# X13_Power_Distribution_B.net
KiCad netlist of a schematic drawn in EAGLE
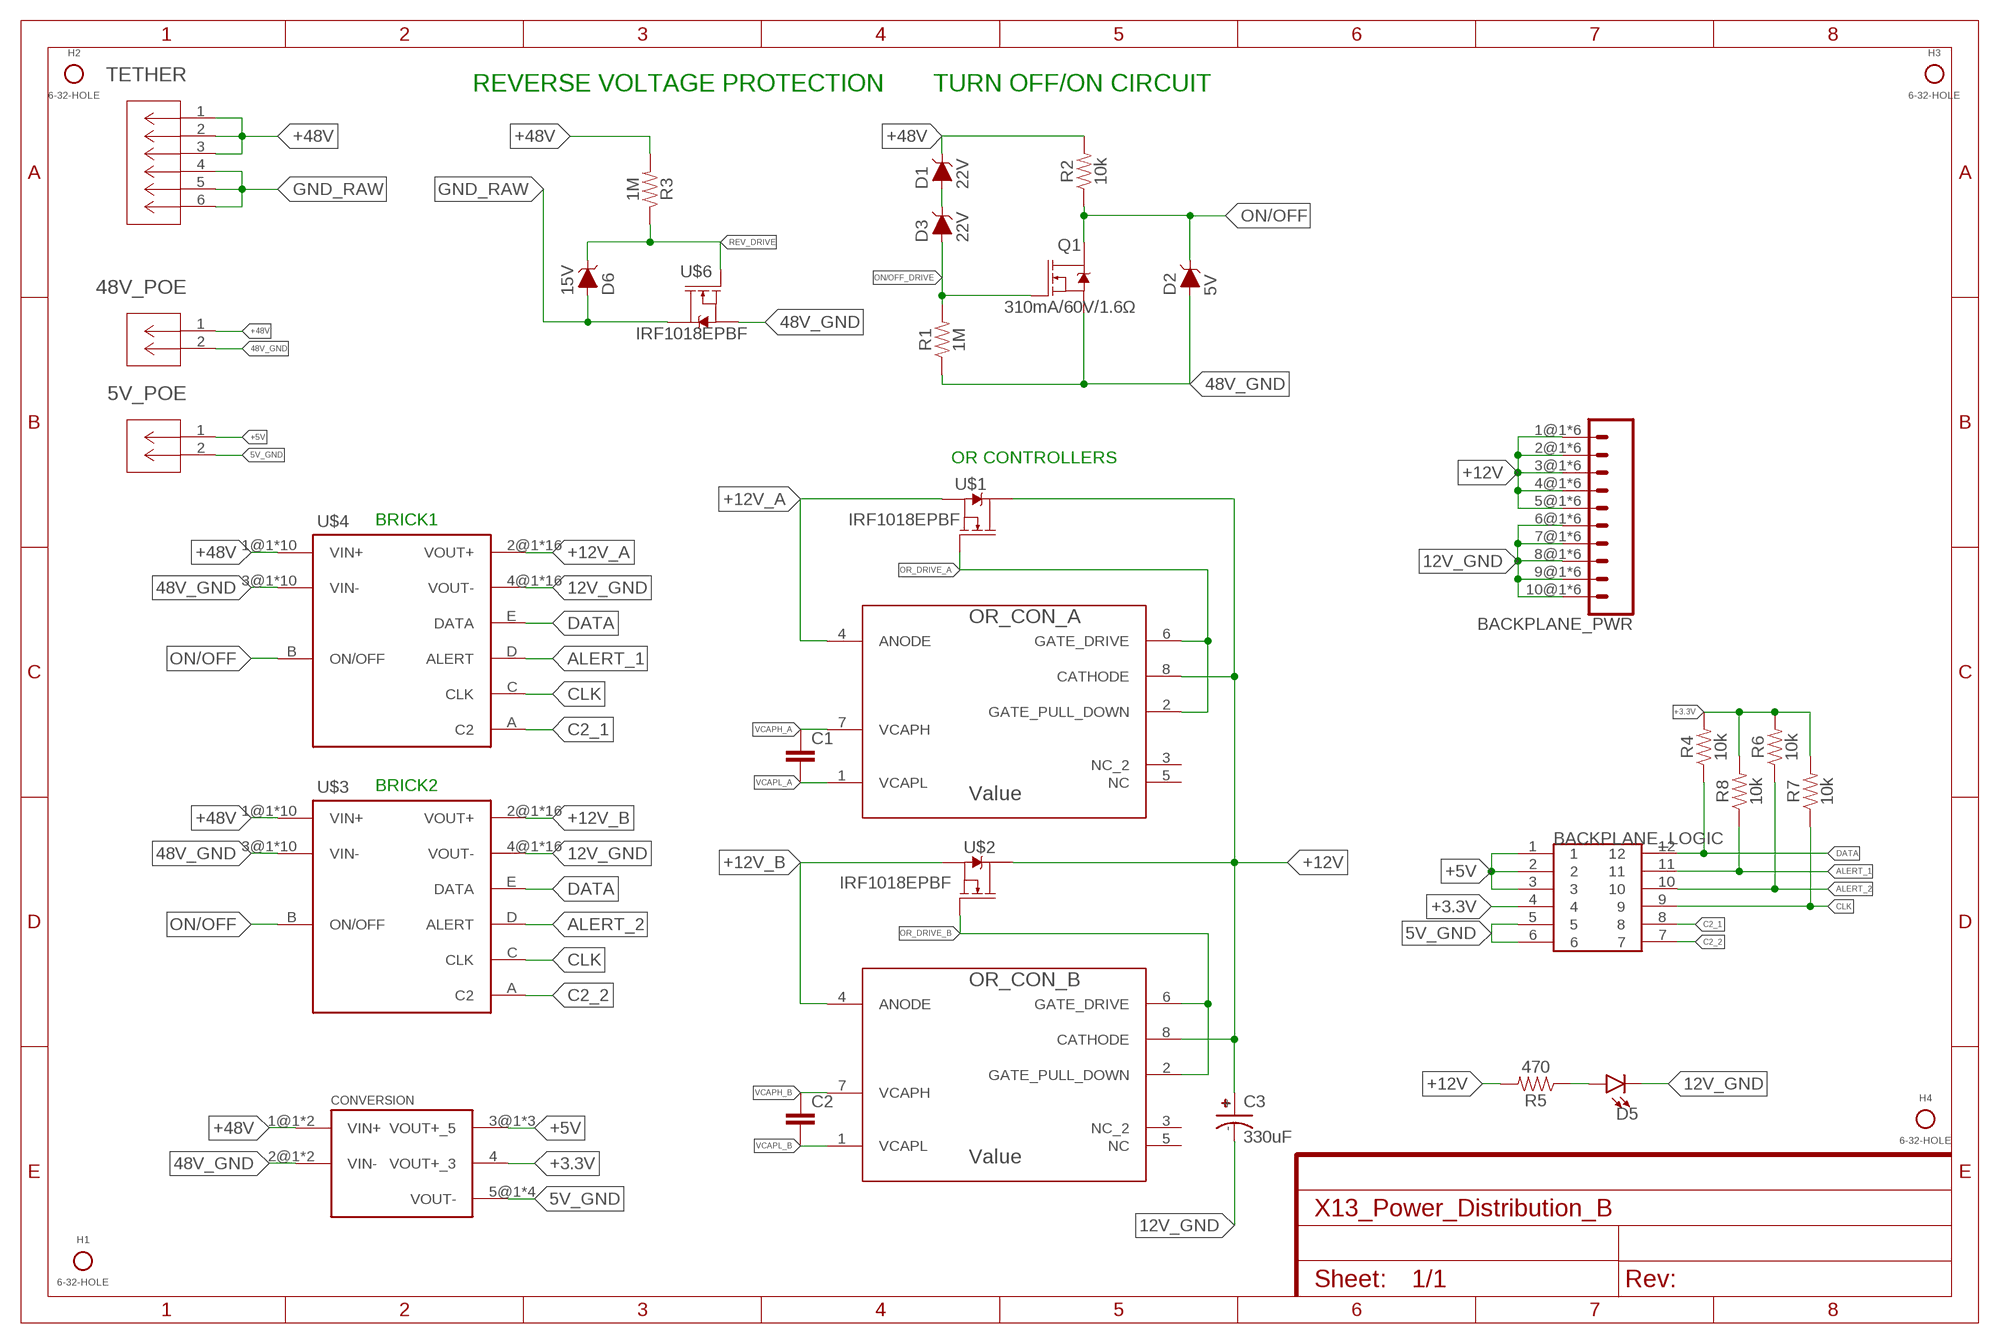
[diagram p0: schematic, sheet 1]

(export (version "E")
  (design (tool "Eeschema 10.0.6"))
  (components
    (comp (ref "5V_POE")
      (value "POE_TERMINAL")
      (footprint "eagle-import:CONN2_282834-2_TEC")
      (fields
        (field (name "MANUFACTURER_PART_NUMBER") "282834-2")
        (field (name "COPYRIGHT") "Copyright (C) 2016 Accelerated Designs. All rights reserved")
      )
      (libsource (lib "eagle-import") (part "POE_TERMINAL"))
    )
    (comp (ref "48V_POE")
      (value "POE_TERMINAL")
      (footprint "eagle-import:CONN2_282834-2_TEC")
      (fields
        (field (name "MANUFACTURER_PART_NUMBER") "282834-2")
        (field (name "COPYRIGHT") "Copyright (C) 2016 Accelerated Designs. All rights reserved")
      )
      (libsource (lib "eagle-import") (part "POE_TERMINAL"))
    )
    (comp (ref "BACKPLANE_LOGIC")
      (value "IPL1-107-01-L-D-RE-P")
      (footprint "eagle-import:IPL1-107-01-L-D-RE-P")
      (libsource (lib "eagle-import") (part "IPL1-107-01-L-D-RE-P"))
    )
    (comp (ref "BACKPLANE_PWR")
      (value "MPPT-10-01-01-L-RA-SD")
      (footprint "eagle-import:MPPT-10-01-01-L-RA-SD")
      (libsource (lib "eagle-import") (part "MPPT-10-01-01-L-RA-SD"))
    )
    (comp (ref "C1")
      (value "0.1UF-0603-100V-10%")
      (footprint "eagle-import:0603")
      (libsource (lib "eagle-import") (part "0.1UF-0603-100V-10%"))
    )
    (comp (ref "C2")
      (value "0.1UF-0603-100V-10%")
      (footprint "eagle-import:0603")
      (libsource (lib "eagle-import") (part "0.1UF-0603-100V-10%"))
    )
    (comp (ref "C3")
      (value "330uF")
      (footprint "eagle-import:CAPAE1030X1050N")
      (fields
        (field (name "ARROW_PART_NUMBER") "UCM1H331MNL1GS")
        (field (name "MOUSER_PART_NUMBER") "647-UCM1H331MNL1GS")
      )
      (libsource (lib "eagle-import") (part "UCM1H331MNL1GS"))
    )
    (comp (ref "CONVERSION")
      (value "DIST2CON")
      (footprint "eagle-import:DIST2CON")
      (libsource (lib "eagle-import") (part "DIST2CON"))
    )
    (comp (ref "D1")
      (value "22V")
      (footprint "eagle-import:SOD-323")
      (libsource (lib "eagle-import") (part "DIODE-ZENER-BZT52C3V6S"))
    )
    (comp (ref "D2")
      (value "5V")
      (footprint "eagle-import:SOD-323")
      (libsource (lib "eagle-import") (part "DIODE-ZENER-BZT52C3V6S"))
    )
    (comp (ref "D3")
      (value "22V")
      (footprint "eagle-import:SOD-323")
      (libsource (lib "eagle-import") (part "DIODE-ZENER-BZT52C3V6S"))
    )
    (comp (ref "D5")
      (value "LED0603")
      (footprint "eagle-import:LED-0603")
      (libsource (lib "eagle-import") (part "LED0603"))
    )
    (comp (ref "D6")
      (value "15V")
      (footprint "eagle-import:SOD-323")
      (libsource (lib "eagle-import") (part "DIODE-ZENER-BZT52C3V6S"))
    )
    (comp (ref "H1")
      (value "6-32-HOLE")
      (footprint "eagle-import:6-32-HOLE")
      (libsource (lib "eagle-import") (part "6-32-HOLE"))
    )
    (comp (ref "H2")
      (value "6-32-HOLE")
      (footprint "eagle-import:6-32-HOLE")
      (libsource (lib "eagle-import") (part "6-32-HOLE"))
    )
    (comp (ref "H3")
      (value "6-32-HOLE")
      (footprint "eagle-import:6-32-HOLE")
      (libsource (lib "eagle-import") (part "6-32-HOLE"))
    )
    (comp (ref "H4")
      (value "6-32-HOLE")
      (footprint "eagle-import:6-32-HOLE")
      (libsource (lib "eagle-import") (part "6-32-HOLE"))
    )
    (comp (ref "OR_CON_A")
      (value "Value")
      (footprint "eagle-import:DGK0008A_M")
      (fields (field (name "MANUFACTURER") "Texas Instruments") (field (name "PARTNUMBER") "LM74610QDGKRQ1"))
      (libsource (lib "eagle-import") (part "DIST_OR_DIODEDGK0008A_M"))
    )
    (comp (ref "OR_CON_B")
      (value "Value")
      (footprint "eagle-import:DGK0008A_M")
      (fields (field (name "MANUFACTURER") "Texas Instruments") (field (name "PARTNUMBER") "LM74610QDGKRQ1"))
      (libsource (lib "eagle-import") (part "DIST_OR_DIODEDGK0008A_M"))
    )
    (comp (ref "Q1")
      (value "310mA/60V/1.6Ω")
      (footprint "eagle-import:SOT323")
      (libsource (lib "eagle-import") (part "MOSFET-NCH-2N7002PW"))
    )
    (comp (ref "R1")
      (value "1M")
      (footprint "eagle-import:0603")
      (fields (field (name "SPICEPREFIX") "R"))
      (libsource (lib "eagle-import") (part "RESISTOR0603"))
    )
    (comp (ref "R2")
      (value "10k")
      (footprint "eagle-import:0603")
      (fields (field (name "SPICEPREFIX") "R"))
      (libsource (lib "eagle-import") (part "RESISTOR0603"))
    )
    (comp (ref "R3")
      (value "1M")
      (footprint "eagle-import:0603")
      (libsource (lib "eagle-import") (part "RESISTOR0603"))
    )
    (comp (ref "R4")
      (value "10k")
      (footprint "eagle-import:0603")
      (libsource (lib "eagle-import") (part "RESISTOR0603"))
    )
    (comp (ref "R5")
      (value "470")
      (footprint "eagle-import:0603")
      (libsource (lib "eagle-import") (part "RESISTOR0603"))
    )
    (comp (ref "R6")
      (value "10k")
      (footprint "eagle-import:0603")
      (libsource (lib "eagle-import") (part "RESISTOR0603"))
    )
    (comp (ref "R7")
      (value "10k")
      (footprint "eagle-import:0603")
      (libsource (lib "eagle-import") (part "RESISTOR0603"))
    )
    (comp (ref "R8")
      (value "10k")
      (footprint "eagle-import:0603")
      (libsource (lib "eagle-import") (part "RESISTOR0603"))
    )
    (comp (ref "TETHER")
      (value "48V")
      (footprint "eagle-import:CON6_P5MM_VER_TERM-BLK_TYC")
      (fields (field (name "MANUFACTURER_PART_NUMBER") "796636-6"))
      (libsource (lib "eagle-import") (part "DIST_TO_TETHER"))
    )
    (comp (ref "U$1")
      (value "IRF1018EPBF")
      (footprint "eagle-import:TO263")
      (libsource (lib "eagle-import") (part "IRF1018EPBF"))
    )
    (comp (ref "U$2")
      (value "IRF1018EPBF")
      (footprint "eagle-import:TO263")
      (libsource (lib "eagle-import") (part "IRF1018EPBF"))
    )
    (comp (ref "U$3")
      (value "DIST2BRICK_B")
      (footprint "eagle-import:DIST2BRICK_B")
      (libsource (lib "eagle-import") (part "DIST2BRICK_B"))
    )
    (comp (ref "U$4")
      (value "DIST2BRICK_B")
      (footprint "eagle-import:DIST2BRICK_B")
      (libsource (lib "eagle-import") (part "DIST2BRICK_B"))
    )
    (comp (ref "U$6")
      (value "IRF1018EPBF")
      (footprint "eagle-import:TO263")
      (libsource (lib "eagle-import") (part "IRF1018EPBF"))
    )
  )
  (nets
    (net (code "1") (name "+3.3V") (class "Default")
      (node (ref "BACKPLANE_LOGIC") (pin "4") (pinfunction "4_4") (pintype "bidirectional"))
      (node (ref "CONVERSION") (pin "4") (pinfunction "VOUT+_3_4") (pintype "bidirectional"))
      (node (ref "R4") (pin "2") (pinfunction "2_2") (pintype "passive"))
      (node (ref "R6") (pin "2") (pinfunction "2_2") (pintype "passive"))
      (node (ref "R7") (pin "2") (pinfunction "2_2") (pintype "passive"))
      (node (ref "R8") (pin "2") (pinfunction "2_2") (pintype "passive"))
    )
    (net (code "2") (name "+5V") (class "Default")
      (node (ref "5V_POE") (pin "1") (pinfunction "1_1") (pintype "passive"))
      (node (ref "BACKPLANE_LOGIC") (pin "1") (pinfunction "1_1") (pintype "bidirectional"))
      (node (ref "BACKPLANE_LOGIC") (pin "2") (pinfunction "2_2") (pintype "bidirectional"))
      (node (ref "BACKPLANE_LOGIC") (pin "3") (pinfunction "3_3") (pintype "bidirectional"))
      (node (ref "CONVERSION") (pin "3@1") (pinfunction "VOUT+_5_3@1") (pintype "bidirectional"))
      (node (ref "CONVERSION") (pin "3@2") (pinfunction "VOUT+_5_3@2") (pintype "bidirectional"))
      (node (ref "CONVERSION") (pin "3@3") (pinfunction "VOUT+_5_3@3") (pintype "bidirectional"))
    )
    (net (code "3") (name "+12V") (class "Default")
      (node (ref "BACKPLANE_PWR") (pin "1@1") (pinfunction "1_1@1") (pintype "passive"))
      (node (ref "BACKPLANE_PWR") (pin "1@2") (pinfunction "1_1@2") (pintype "passive"))
      (node (ref "BACKPLANE_PWR") (pin "1@3") (pinfunction "1_1@3") (pintype "passive"))
      (node (ref "BACKPLANE_PWR") (pin "1@4") (pinfunction "1_1@4") (pintype "passive"))
      (node (ref "BACKPLANE_PWR") (pin "1@5") (pinfunction "1_1@5") (pintype "passive"))
      (node (ref "BACKPLANE_PWR") (pin "1@6") (pinfunction "1_1@6") (pintype "passive"))
      (node (ref "BACKPLANE_PWR") (pin "2@1") (pinfunction "2_2@1") (pintype "passive"))
      (node (ref "BACKPLANE_PWR") (pin "2@2") (pinfunction "2_2@2") (pintype "passive"))
      (node (ref "BACKPLANE_PWR") (pin "2@3") (pinfunction "2_2@3") (pintype "passive"))
      (node (ref "BACKPLANE_PWR") (pin "2@4") (pinfunction "2_2@4") (pintype "passive"))
      (node (ref "BACKPLANE_PWR") (pin "2@5") (pinfunction "2_2@5") (pintype "passive"))
      (node (ref "BACKPLANE_PWR") (pin "2@6") (pinfunction "2_2@6") (pintype "passive"))
      (node (ref "BACKPLANE_PWR") (pin "3@1") (pinfunction "3_3@1") (pintype "passive"))
      (node (ref "BACKPLANE_PWR") (pin "3@2") (pinfunction "3_3@2") (pintype "passive"))
      (node (ref "BACKPLANE_PWR") (pin "3@3") (pinfunction "3_3@3") (pintype "passive"))
      (node (ref "BACKPLANE_PWR") (pin "3@4") (pinfunction "3_3@4") (pintype "passive"))
      (node (ref "BACKPLANE_PWR") (pin "3@5") (pinfunction "3_3@5") (pintype "passive"))
      (node (ref "BACKPLANE_PWR") (pin "3@6") (pinfunction "3_3@6") (pintype "passive"))
      (node (ref "BACKPLANE_PWR") (pin "4@1") (pinfunction "4_4@1") (pintype "passive"))
      (node (ref "BACKPLANE_PWR") (pin "4@2") (pinfunction "4_4@2") (pintype "passive"))
      (node (ref "BACKPLANE_PWR") (pin "4@3") (pinfunction "4_4@3") (pintype "passive"))
      (node (ref "BACKPLANE_PWR") (pin "4@4") (pinfunction "4_4@4") (pintype "passive"))
      (node (ref "BACKPLANE_PWR") (pin "4@5") (pinfunction "4_4@5") (pintype "passive"))
      (node (ref "BACKPLANE_PWR") (pin "4@6") (pinfunction "4_4@6") (pintype "passive"))
      (node (ref "BACKPLANE_PWR") (pin "5@1") (pinfunction "5_5@1") (pintype "passive"))
      (node (ref "BACKPLANE_PWR") (pin "5@2") (pinfunction "5_5@2") (pintype "passive"))
      (node (ref "BACKPLANE_PWR") (pin "5@3") (pinfunction "5_5@3") (pintype "passive"))
      (node (ref "BACKPLANE_PWR") (pin "5@4") (pinfunction "5_5@4") (pintype "passive"))
      (node (ref "BACKPLANE_PWR") (pin "5@5") (pinfunction "5_5@5") (pintype "passive"))
      (node (ref "BACKPLANE_PWR") (pin "5@6") (pinfunction "5_5@6") (pintype "passive"))
      (node (ref "C3") (pin "+") (pinfunction "+_+") (pintype "bidirectional"))
      (node (ref "OR_CON_A") (pin "8") (pinfunction "CATHODE_8") (pintype "output"))
      (node (ref "OR_CON_B") (pin "8") (pinfunction "CATHODE_8") (pintype "output"))
      (node (ref "R5") (pin "2") (pinfunction "2_2") (pintype "passive"))
      (node (ref "U$1") (pin "3") (pinfunction "D_3") (pintype "bidirectional"))
      (node (ref "U$2") (pin "3") (pinfunction "D_3") (pintype "bidirectional"))
    )
    (net (code "4") (name "+12V_A") (class "Default")
      (node (ref "OR_CON_A") (pin "4") (pinfunction "ANODE_4") (pintype "power_in"))
      (node (ref "U$1") (pin "2") (pinfunction "S_2") (pintype "bidirectional"))
      (node (ref "U$4") (pin "2@1") (pinfunction "VOUT+_2@1") (pintype "bidirectional"))
      (node (ref "U$4") (pin "2@10") (pinfunction "VOUT+_2@10") (pintype "bidirectional"))
      (node (ref "U$4") (pin "2@11") (pinfunction "VOUT+_2@11") (pintype "bidirectional"))
      (node (ref "U$4") (pin "2@12") (pinfunction "VOUT+_2@12") (pintype "bidirectional"))
      (node (ref "U$4") (pin "2@13") (pinfunction "VOUT+_2@13") (pintype "bidirectional"))
      (node (ref "U$4") (pin "2@14") (pinfunction "VOUT+_2@14") (pintype "bidirectional"))
      (node (ref "U$4") (pin "2@15") (pinfunction "VOUT+_2@15") (pintype "bidirectional"))
      (node (ref "U$4") (pin "2@16") (pinfunction "VOUT+_2@16") (pintype "bidirectional"))
      (node (ref "U$4") (pin "2@2") (pinfunction "VOUT+_2@2") (pintype "bidirectional"))
      (node (ref "U$4") (pin "2@3") (pinfunction "VOUT+_2@3") (pintype "bidirectional"))
      (node (ref "U$4") (pin "2@4") (pinfunction "VOUT+_2@4") (pintype "bidirectional"))
      (node (ref "U$4") (pin "2@5") (pinfunction "VOUT+_2@5") (pintype "bidirectional"))
      (node (ref "U$4") (pin "2@6") (pinfunction "VOUT+_2@6") (pintype "bidirectional"))
      (node (ref "U$4") (pin "2@7") (pinfunction "VOUT+_2@7") (pintype "bidirectional"))
      (node (ref "U$4") (pin "2@8") (pinfunction "VOUT+_2@8") (pintype "bidirectional"))
      (node (ref "U$4") (pin "2@9") (pinfunction "VOUT+_2@9") (pintype "bidirectional"))
    )
    (net (code "5") (name "+12V_B") (class "Default")
      (node (ref "OR_CON_B") (pin "4") (pinfunction "ANODE_4") (pintype "power_in"))
      (node (ref "U$2") (pin "2") (pinfunction "S_2") (pintype "bidirectional"))
      (node (ref "U$3") (pin "2@1") (pinfunction "VOUT+_2@1") (pintype "bidirectional"))
      (node (ref "U$3") (pin "2@10") (pinfunction "VOUT+_2@10") (pintype "bidirectional"))
      (node (ref "U$3") (pin "2@11") (pinfunction "VOUT+_2@11") (pintype "bidirectional"))
      (node (ref "U$3") (pin "2@12") (pinfunction "VOUT+_2@12") (pintype "bidirectional"))
      (node (ref "U$3") (pin "2@13") (pinfunction "VOUT+_2@13") (pintype "bidirectional"))
      (node (ref "U$3") (pin "2@14") (pinfunction "VOUT+_2@14") (pintype "bidirectional"))
      (node (ref "U$3") (pin "2@15") (pinfunction "VOUT+_2@15") (pintype "bidirectional"))
      (node (ref "U$3") (pin "2@16") (pinfunction "VOUT+_2@16") (pintype "bidirectional"))
      (node (ref "U$3") (pin "2@2") (pinfunction "VOUT+_2@2") (pintype "bidirectional"))
      (node (ref "U$3") (pin "2@3") (pinfunction "VOUT+_2@3") (pintype "bidirectional"))
      (node (ref "U$3") (pin "2@4") (pinfunction "VOUT+_2@4") (pintype "bidirectional"))
      (node (ref "U$3") (pin "2@5") (pinfunction "VOUT+_2@5") (pintype "bidirectional"))
      (node (ref "U$3") (pin "2@6") (pinfunction "VOUT+_2@6") (pintype "bidirectional"))
      (node (ref "U$3") (pin "2@7") (pinfunction "VOUT+_2@7") (pintype "bidirectional"))
      (node (ref "U$3") (pin "2@8") (pinfunction "VOUT+_2@8") (pintype "bidirectional"))
      (node (ref "U$3") (pin "2@9") (pinfunction "VOUT+_2@9") (pintype "bidirectional"))
    )
    (net (code "6") (name "+48V") (class "Default")
      (node (ref "48V_POE") (pin "1") (pinfunction "1_1") (pintype "passive"))
      (node (ref "CONVERSION") (pin "1@1") (pinfunction "VIN+_1@1") (pintype "bidirectional"))
      (node (ref "CONVERSION") (pin "1@2") (pinfunction "VIN+_1@2") (pintype "bidirectional"))
      (node (ref "D1") (pin "C") (pinfunction "C_C") (pintype "passive"))
      (node (ref "R2") (pin "2") (pinfunction "2_2") (pintype "passive"))
      (node (ref "R3") (pin "2") (pinfunction "2_2") (pintype "passive"))
      (node (ref "TETHER") (pin "1") (pinfunction "1_1") (pintype "passive"))
      (node (ref "TETHER") (pin "2") (pinfunction "2_2") (pintype "passive"))
      (node (ref "TETHER") (pin "3") (pinfunction "3_3") (pintype "passive"))
      (node (ref "U$3") (pin "1@1") (pinfunction "VIN+_1@1") (pintype "bidirectional"))
      (node (ref "U$3") (pin "1@10") (pinfunction "VIN+_1@10") (pintype "bidirectional"))
      (node (ref "U$3") (pin "1@2") (pinfunction "VIN+_1@2") (pintype "bidirectional"))
      (node (ref "U$3") (pin "1@3") (pinfunction "VIN+_1@3") (pintype "bidirectional"))
      (node (ref "U$3") (pin "1@4") (pinfunction "VIN+_1@4") (pintype "bidirectional"))
      (node (ref "U$3") (pin "1@5") (pinfunction "VIN+_1@5") (pintype "bidirectional"))
      (node (ref "U$3") (pin "1@6") (pinfunction "VIN+_1@6") (pintype "bidirectional"))
      (node (ref "U$3") (pin "1@7") (pinfunction "VIN+_1@7") (pintype "bidirectional"))
      (node (ref "U$3") (pin "1@8") (pinfunction "VIN+_1@8") (pintype "bidirectional"))
      (node (ref "U$3") (pin "1@9") (pinfunction "VIN+_1@9") (pintype "bidirectional"))
      (node (ref "U$4") (pin "1@1") (pinfunction "VIN+_1@1") (pintype "bidirectional"))
      (node (ref "U$4") (pin "1@10") (pinfunction "VIN+_1@10") (pintype "bidirectional"))
      (node (ref "U$4") (pin "1@2") (pinfunction "VIN+_1@2") (pintype "bidirectional"))
      (node (ref "U$4") (pin "1@3") (pinfunction "VIN+_1@3") (pintype "bidirectional"))
      (node (ref "U$4") (pin "1@4") (pinfunction "VIN+_1@4") (pintype "bidirectional"))
      (node (ref "U$4") (pin "1@5") (pinfunction "VIN+_1@5") (pintype "bidirectional"))
      (node (ref "U$4") (pin "1@6") (pinfunction "VIN+_1@6") (pintype "bidirectional"))
      (node (ref "U$4") (pin "1@7") (pinfunction "VIN+_1@7") (pintype "bidirectional"))
      (node (ref "U$4") (pin "1@8") (pinfunction "VIN+_1@8") (pintype "bidirectional"))
      (node (ref "U$4") (pin "1@9") (pinfunction "VIN+_1@9") (pintype "bidirectional"))
    )
    (net (code "7") (name "5V_GND") (class "Default")
      (node (ref "5V_POE") (pin "2") (pinfunction "2_2") (pintype "passive"))
      (node (ref "BACKPLANE_LOGIC") (pin "5") (pinfunction "5_5") (pintype "bidirectional"))
      (node (ref "BACKPLANE_LOGIC") (pin "6") (pinfunction "6_6") (pintype "bidirectional"))
      (node (ref "CONVERSION") (pin "5@1") (pinfunction "VOUT-_5@1") (pintype "bidirectional"))
      (node (ref "CONVERSION") (pin "5@2") (pinfunction "VOUT-_5@2") (pintype "bidirectional"))
      (node (ref "CONVERSION") (pin "5@3") (pinfunction "VOUT-_5@3") (pintype "bidirectional"))
      (node (ref "CONVERSION") (pin "5@4") (pinfunction "VOUT-_5@4") (pintype "bidirectional"))
    )
    (net (code "8") (name "12V_GND") (class "Default")
      (node (ref "BACKPLANE_PWR") (pin "10@1") (pinfunction "10_10@1") (pintype "passive"))
      (node (ref "BACKPLANE_PWR") (pin "10@2") (pinfunction "10_10@2") (pintype "passive"))
      (node (ref "BACKPLANE_PWR") (pin "10@3") (pinfunction "10_10@3") (pintype "passive"))
      (node (ref "BACKPLANE_PWR") (pin "10@4") (pinfunction "10_10@4") (pintype "passive"))
      (node (ref "BACKPLANE_PWR") (pin "10@5") (pinfunction "10_10@5") (pintype "passive"))
      (node (ref "BACKPLANE_PWR") (pin "10@6") (pinfunction "10_10@6") (pintype "passive"))
      (node (ref "BACKPLANE_PWR") (pin "6@1") (pinfunction "6_6@1") (pintype "passive"))
      (node (ref "BACKPLANE_PWR") (pin "6@2") (pinfunction "6_6@2") (pintype "passive"))
      (node (ref "BACKPLANE_PWR") (pin "6@3") (pinfunction "6_6@3") (pintype "passive"))
      (node (ref "BACKPLANE_PWR") (pin "6@4") (pinfunction "6_6@4") (pintype "passive"))
      (node (ref "BACKPLANE_PWR") (pin "6@5") (pinfunction "6_6@5") (pintype "passive"))
      (node (ref "BACKPLANE_PWR") (pin "6@6") (pinfunction "6_6@6") (pintype "passive"))
      (node (ref "BACKPLANE_PWR") (pin "7@1") (pinfunction "7_7@1") (pintype "passive"))
      (node (ref "BACKPLANE_PWR") (pin "7@2") (pinfunction "7_7@2") (pintype "passive"))
      (node (ref "BACKPLANE_PWR") (pin "7@3") (pinfunction "7_7@3") (pintype "passive"))
      (node (ref "BACKPLANE_PWR") (pin "7@4") (pinfunction "7_7@4") (pintype "passive"))
      (node (ref "BACKPLANE_PWR") (pin "7@5") (pinfunction "7_7@5") (pintype "passive"))
      (node (ref "BACKPLANE_PWR") (pin "7@6") (pinfunction "7_7@6") (pintype "passive"))
      (node (ref "BACKPLANE_PWR") (pin "8@1") (pinfunction "8_8@1") (pintype "passive"))
      (node (ref "BACKPLANE_PWR") (pin "8@2") (pinfunction "8_8@2") (pintype "passive"))
      (node (ref "BACKPLANE_PWR") (pin "8@3") (pinfunction "8_8@3") (pintype "passive"))
      (node (ref "BACKPLANE_PWR") (pin "8@4") (pinfunction "8_8@4") (pintype "passive"))
      (node (ref "BACKPLANE_PWR") (pin "8@5") (pinfunction "8_8@5") (pintype "passive"))
      (node (ref "BACKPLANE_PWR") (pin "8@6") (pinfunction "8_8@6") (pintype "passive"))
      (node (ref "BACKPLANE_PWR") (pin "9@1") (pinfunction "9_9@1") (pintype "passive"))
      (node (ref "BACKPLANE_PWR") (pin "9@2") (pinfunction "9_9@2") (pintype "passive"))
      (node (ref "BACKPLANE_PWR") (pin "9@3") (pinfunction "9_9@3") (pintype "passive"))
      (node (ref "BACKPLANE_PWR") (pin "9@4") (pinfunction "9_9@4") (pintype "passive"))
      (node (ref "BACKPLANE_PWR") (pin "9@5") (pinfunction "9_9@5") (pintype "passive"))
      (node (ref "BACKPLANE_PWR") (pin "9@6") (pinfunction "9_9@6") (pintype "passive"))
      (node (ref "C3") (pin "-") (pinfunction "-_-") (pintype "bidirectional"))
      (node (ref "D5") (pin "C") (pinfunction "C_C") (pintype "passive"))
      (node (ref "U$3") (pin "4@1") (pinfunction "VOUT-_4@1") (pintype "bidirectional"))
      (node (ref "U$3") (pin "4@10") (pinfunction "VOUT-_4@10") (pintype "bidirectional"))
      (node (ref "U$3") (pin "4@11") (pinfunction "VOUT-_4@11") (pintype "bidirectional"))
      (node (ref "U$3") (pin "4@12") (pinfunction "VOUT-_4@12") (pintype "bidirectional"))
      (node (ref "U$3") (pin "4@13") (pinfunction "VOUT-_4@13") (pintype "bidirectional"))
      (node (ref "U$3") (pin "4@14") (pinfunction "VOUT-_4@14") (pintype "bidirectional"))
      (node (ref "U$3") (pin "4@15") (pinfunction "VOUT-_4@15") (pintype "bidirectional"))
      (node (ref "U$3") (pin "4@16") (pinfunction "VOUT-_4@16") (pintype "bidirectional"))
      (node (ref "U$3") (pin "4@2") (pinfunction "VOUT-_4@2") (pintype "bidirectional"))
      (node (ref "U$3") (pin "4@3") (pinfunction "VOUT-_4@3") (pintype "bidirectional"))
      (node (ref "U$3") (pin "4@4") (pinfunction "VOUT-_4@4") (pintype "bidirectional"))
      (node (ref "U$3") (pin "4@5") (pinfunction "VOUT-_4@5") (pintype "bidirectional"))
      (node (ref "U$3") (pin "4@6") (pinfunction "VOUT-_4@6") (pintype "bidirectional"))
      (node (ref "U$3") (pin "4@7") (pinfunction "VOUT-_4@7") (pintype "bidirectional"))
      (node (ref "U$3") (pin "4@8") (pinfunction "VOUT-_4@8") (pintype "bidirectional"))
      (node (ref "U$3") (pin "4@9") (pinfunction "VOUT-_4@9") (pintype "bidirectional"))
      (node (ref "U$4") (pin "4@1") (pinfunction "VOUT-_4@1") (pintype "bidirectional"))
      (node (ref "U$4") (pin "4@10") (pinfunction "VOUT-_4@10") (pintype "bidirectional"))
      (node (ref "U$4") (pin "4@11") (pinfunction "VOUT-_4@11") (pintype "bidirectional"))
      (node (ref "U$4") (pin "4@12") (pinfunction "VOUT-_4@12") (pintype "bidirectional"))
      (node (ref "U$4") (pin "4@13") (pinfunction "VOUT-_4@13") (pintype "bidirectional"))
      (node (ref "U$4") (pin "4@14") (pinfunction "VOUT-_4@14") (pintype "bidirectional"))
      (node (ref "U$4") (pin "4@15") (pinfunction "VOUT-_4@15") (pintype "bidirectional"))
      (node (ref "U$4") (pin "4@16") (pinfunction "VOUT-_4@16") (pintype "bidirectional"))
      (node (ref "U$4") (pin "4@2") (pinfunction "VOUT-_4@2") (pintype "bidirectional"))
      (node (ref "U$4") (pin "4@3") (pinfunction "VOUT-_4@3") (pintype "bidirectional"))
      (node (ref "U$4") (pin "4@4") (pinfunction "VOUT-_4@4") (pintype "bidirectional"))
      (node (ref "U$4") (pin "4@5") (pinfunction "VOUT-_4@5") (pintype "bidirectional"))
      (node (ref "U$4") (pin "4@6") (pinfunction "VOUT-_4@6") (pintype "bidirectional"))
      (node (ref "U$4") (pin "4@7") (pinfunction "VOUT-_4@7") (pintype "bidirectional"))
      (node (ref "U$4") (pin "4@8") (pinfunction "VOUT-_4@8") (pintype "bidirectional"))
      (node (ref "U$4") (pin "4@9") (pinfunction "VOUT-_4@9") (pintype "bidirectional"))
    )
    (net (code "9") (name "48V_GND") (class "Default")
      (node (ref "48V_POE") (pin "2") (pinfunction "2_2") (pintype "passive"))
      (node (ref "CONVERSION") (pin "2@1") (pinfunction "VIN-_2@1") (pintype "bidirectional"))
      (node (ref "CONVERSION") (pin "2@2") (pinfunction "VIN-_2@2") (pintype "bidirectional"))
      (node (ref "D2") (pin "A") (pinfunction "A_A") (pintype "passive"))
      (node (ref "Q1") (pin "2") (pinfunction "S_2") (pintype "bidirectional"))
      (node (ref "R1") (pin "1") (pinfunction "1_1") (pintype "passive"))
      (node (ref "U$3") (pin "3@1") (pinfunction "VIN-_3@1") (pintype "bidirectional"))
      (node (ref "U$3") (pin "3@10") (pinfunction "VIN-_3@10") (pintype "bidirectional"))
      (node (ref "U$3") (pin "3@2") (pinfunction "VIN-_3@2") (pintype "bidirectional"))
      (node (ref "U$3") (pin "3@3") (pinfunction "VIN-_3@3") (pintype "bidirectional"))
      (node (ref "U$3") (pin "3@4") (pinfunction "VIN-_3@4") (pintype "bidirectional"))
      (node (ref "U$3") (pin "3@5") (pinfunction "VIN-_3@5") (pintype "bidirectional"))
      (node (ref "U$3") (pin "3@6") (pinfunction "VIN-_3@6") (pintype "bidirectional"))
      (node (ref "U$3") (pin "3@7") (pinfunction "VIN-_3@7") (pintype "bidirectional"))
      (node (ref "U$3") (pin "3@8") (pinfunction "VIN-_3@8") (pintype "bidirectional"))
      (node (ref "U$3") (pin "3@9") (pinfunction "VIN-_3@9") (pintype "bidirectional"))
      (node (ref "U$4") (pin "3@1") (pinfunction "VIN-_3@1") (pintype "bidirectional"))
      (node (ref "U$4") (pin "3@10") (pinfunction "VIN-_3@10") (pintype "bidirectional"))
      (node (ref "U$4") (pin "3@2") (pinfunction "VIN-_3@2") (pintype "bidirectional"))
      (node (ref "U$4") (pin "3@3") (pinfunction "VIN-_3@3") (pintype "bidirectional"))
      (node (ref "U$4") (pin "3@4") (pinfunction "VIN-_3@4") (pintype "bidirectional"))
      (node (ref "U$4") (pin "3@5") (pinfunction "VIN-_3@5") (pintype "bidirectional"))
      (node (ref "U$4") (pin "3@6") (pinfunction "VIN-_3@6") (pintype "bidirectional"))
      (node (ref "U$4") (pin "3@7") (pinfunction "VIN-_3@7") (pintype "bidirectional"))
      (node (ref "U$4") (pin "3@8") (pinfunction "VIN-_3@8") (pintype "bidirectional"))
      (node (ref "U$4") (pin "3@9") (pinfunction "VIN-_3@9") (pintype "bidirectional"))
      (node (ref "U$6") (pin "2") (pinfunction "S_2") (pintype "bidirectional"))
    )
    (net (code "10") (name "ALERT_1") (class "Default")
      (node (ref "BACKPLANE_LOGIC") (pin "11") (pinfunction "11_11") (pintype "bidirectional"))
      (node (ref "R8") (pin "1") (pinfunction "1_1") (pintype "passive"))
      (node (ref "U$4") (pin "D") (pinfunction "ALERT_D") (pintype "bidirectional"))
    )
    (net (code "11") (name "ALERT_2") (class "Default")
      (node (ref "BACKPLANE_LOGIC") (pin "10") (pinfunction "10_10") (pintype "bidirectional"))
      (node (ref "R6") (pin "1") (pinfunction "1_1") (pintype "passive"))
      (node (ref "U$3") (pin "D") (pinfunction "ALERT_D") (pintype "bidirectional"))
    )
    (net (code "12") (name "C2_1") (class "Default")
      (node (ref "BACKPLANE_LOGIC") (pin "8") (pinfunction "8_8") (pintype "bidirectional"))
      (node (ref "U$4") (pin "A") (pinfunction "C2_A") (pintype "bidirectional"))
    )
    (net (code "13") (name "C2_2") (class "Default")
      (node (ref "BACKPLANE_LOGIC") (pin "7") (pinfunction "7_7") (pintype "bidirectional"))
      (node (ref "U$3") (pin "A") (pinfunction "C2_A") (pintype "bidirectional"))
    )
    (net (code "14") (name "CLK") (class "Default")
      (node (ref "BACKPLANE_LOGIC") (pin "9") (pinfunction "9_9") (pintype "bidirectional"))
      (node (ref "R7") (pin "1") (pinfunction "1_1") (pintype "passive"))
      (node (ref "U$3") (pin "C") (pinfunction "CLK_C") (pintype "bidirectional"))
      (node (ref "U$4") (pin "C") (pinfunction "CLK_C") (pintype "bidirectional"))
    )
    (net (code "15") (name "DATA") (class "Default")
      (node (ref "BACKPLANE_LOGIC") (pin "12") (pinfunction "12_12") (pintype "bidirectional"))
      (node (ref "R4") (pin "1") (pinfunction "1_1") (pintype "passive"))
      (node (ref "U$3") (pin "E") (pinfunction "DATA_E") (pintype "bidirectional"))
      (node (ref "U$4") (pin "E") (pinfunction "DATA_E") (pintype "bidirectional"))
    )
    (net (code "16") (name "GND_RAW") (class "Default")
      (node (ref "D6") (pin "A") (pinfunction "A_A") (pintype "passive"))
      (node (ref "TETHER") (pin "4") (pinfunction "4_4") (pintype "passive"))
      (node (ref "TETHER") (pin "5") (pinfunction "5_5") (pintype "passive"))
      (node (ref "TETHER") (pin "6") (pinfunction "6_6") (pintype "passive"))
      (node (ref "U$6") (pin "3") (pinfunction "D_3") (pintype "bidirectional"))
    )
    (net (code "17") (name "Net-(D1-PadA)") (class "Default")
      (node (ref "D1") (pin "A") (pinfunction "A_A") (pintype "passive"))
      (node (ref "D3") (pin "C") (pinfunction "C_C") (pintype "passive"))
    )
    (net (code "18") (name "Net-(D5-PadA)") (class "Default")
      (node (ref "D5") (pin "A") (pinfunction "A_A") (pintype "passive"))
      (node (ref "R5") (pin "1") (pinfunction "1_1") (pintype "passive"))
    )
    (net (code "19") (name "ON{slash}OFF") (class "Default")
      (node (ref "D2") (pin "C") (pinfunction "C_C") (pintype "passive"))
      (node (ref "Q1") (pin "3") (pinfunction "D_3") (pintype "bidirectional"))
      (node (ref "R2") (pin "1") (pinfunction "1_1") (pintype "passive"))
      (node (ref "U$3") (pin "B") (pinfunction "ON/OFF_B") (pintype "bidirectional"))
      (node (ref "U$4") (pin "B") (pinfunction "ON/OFF_B") (pintype "bidirectional"))
    )
    (net (code "20") (name "ON{slash}OFF_DRIVE") (class "Default")
      (node (ref "D3") (pin "A") (pinfunction "A_A") (pintype "passive"))
      (node (ref "Q1") (pin "1") (pinfunction "G_1") (pintype "bidirectional"))
      (node (ref "R1") (pin "2") (pinfunction "2_2") (pintype "passive"))
    )
    (net (code "21") (name "OR_DRIVE_A") (class "Default")
      (node (ref "OR_CON_A") (pin "2") (pinfunction "GATE_PULL_DOWN_2") (pintype "passive"))
      (node (ref "OR_CON_A") (pin "6") (pinfunction "GATE_DRIVE_6") (pintype "output"))
      (node (ref "U$1") (pin "1") (pinfunction "G_1") (pintype "bidirectional"))
    )
    (net (code "22") (name "OR_DRIVE_B") (class "Default")
      (node (ref "OR_CON_B") (pin "2") (pinfunction "GATE_PULL_DOWN_2") (pintype "passive"))
      (node (ref "OR_CON_B") (pin "6") (pinfunction "GATE_DRIVE_6") (pintype "output"))
      (node (ref "U$2") (pin "1") (pinfunction "G_1") (pintype "bidirectional"))
    )
    (net (code "23") (name "REV_DRIVE") (class "Default")
      (node (ref "D6") (pin "C") (pinfunction "C_C") (pintype "passive"))
      (node (ref "R3") (pin "1") (pinfunction "1_1") (pintype "passive"))
      (node (ref "U$6") (pin "1") (pinfunction "G_1") (pintype "bidirectional"))
    )
    (net (code "24") (name "VCAPH_A") (class "Default")
      (node (ref "C1") (pin "1") (pinfunction "1_1") (pintype "passive"))
      (node (ref "OR_CON_A") (pin "7") (pinfunction "VCAPH_7") (pintype "passive"))
    )
    (net (code "25") (name "VCAPH_B") (class "Default")
      (node (ref "C2") (pin "1") (pinfunction "1_1") (pintype "passive"))
      (node (ref "OR_CON_B") (pin "7") (pinfunction "VCAPH_7") (pintype "passive"))
    )
    (net (code "26") (name "VCAPL_A") (class "Default")
      (node (ref "C1") (pin "2") (pinfunction "2_2") (pintype "passive"))
      (node (ref "OR_CON_A") (pin "1") (pinfunction "VCAPL_1") (pintype "passive"))
    )
    (net (code "27") (name "VCAPL_B") (class "Default")
      (node (ref "C2") (pin "2") (pinfunction "2_2") (pintype "passive"))
      (node (ref "OR_CON_B") (pin "1") (pinfunction "VCAPL_1") (pintype "passive"))
    )
    (net (code "28") (name "unconnected-(OR_CON_A-NC-Pad5)") (class "Default")
      (node (ref "OR_CON_A") (pin "5") (pinfunction "NC_5") (pintype "passive"))
    )
    (net (code "29") (name "unconnected-(OR_CON_A-NC_2-Pad3)") (class "Default")
      (node (ref "OR_CON_A") (pin "3") (pinfunction "NC_2_3") (pintype "passive"))
    )
    (net (code "30") (name "unconnected-(OR_CON_B-NC-Pad5)") (class "Default")
      (node (ref "OR_CON_B") (pin "5") (pinfunction "NC_5") (pintype "passive"))
    )
    (net (code "31") (name "unconnected-(OR_CON_B-NC_2-Pad3)") (class "Default")
      (node (ref "OR_CON_B") (pin "3") (pinfunction "NC_2_3") (pintype "passive"))
    )
  )
)
